# Filter_240MHz.net
KiCad netlist of a schematic drawn in Altium Designer
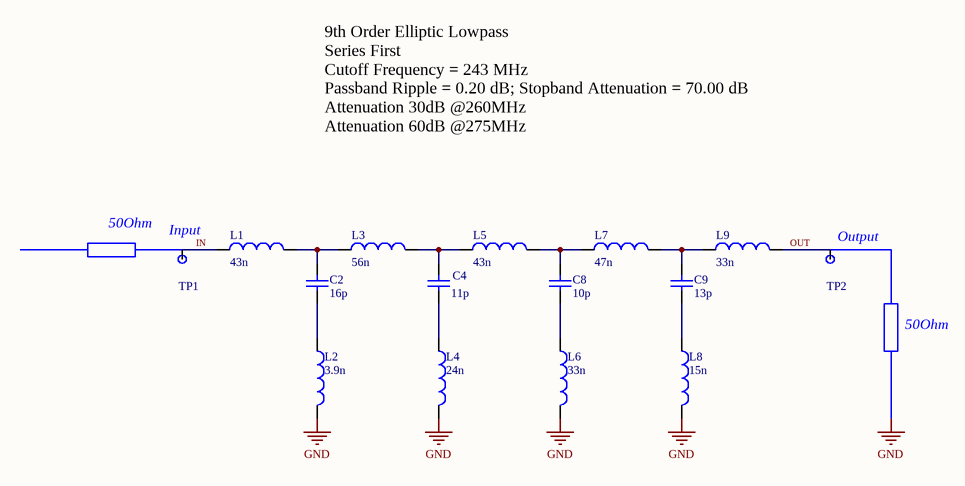
[diagram p0: Filter_240MHz.SchDoc]

(export (version "E")
  (design (tool "Eeschema 10.0.6"))
  (components
    (comp (ref "C2")
      (value "16p")
      (footprint "C0402")
      (description "16p 50V 0402")
      (fields (field (name "PART NUMBER") "CQ0402FRNPO9BN160") (field (name "VOLTAGE") "50V"))
      (libsource (lib "Capacitors") (part "1n_50V_0402"))
    )
    (comp (ref "C4")
      (value "11p")
      (footprint "C0402")
      (description "11p 50V 0402")
      (fields (field (name "PART NUMBER") "CC0402JRNPO9BN110") (field (name "VOLTAGE") "50V"))
      (libsource (lib "Capacitors") (part "1n_50V_0402"))
    )
    (comp (ref "C8")
      (value "10p")
      (footprint "C0402")
      (description "10p 50V 0402")
      (fields (field (name "PART NUMBER") "CQ0402FRNPO9BN100") (field (name "VOLTAGE") "50V"))
      (libsource (lib "Capacitors") (part "1n_50V_0402"))
    )
    (comp (ref "C9")
      (value "13p")
      (footprint "C0402")
      (description "13p 50V 0402")
      (fields (field (name "PART NUMBER") "CC0402JRNPO9BN130") (field (name "VOLTAGE") "50V"))
      (libsource (lib "Capacitors") (part "1n_50V_0402"))
    )
    (comp (ref "L1")
      (value "43n")
      (footprint "R0402")
      (description "43n 0402 0.7Ohm")
      (fields (field (name "PART NUMBER") "0402HM-430EGTS"))
      (libsource (lib "Inductors") (part "0402HC-3N9ECTS"))
    )
    (comp (ref "L2")
      (value "3.9n")
      (footprint "R0402")
      (description "3.9n 0402")
      (fields (field (name "PART NUMBER") "0402HC-3N9ECTS"))
      (libsource (lib "Inductors") (part "0402HC-3N9ECTS"))
    )
    (comp (ref "L3")
      (value "56n")
      (footprint "R0402")
      (description "56n 0402 1.17Ohm")
      (fields (field (name "PART NUMBER") "0402HM-560EGTS"))
      (libsource (lib "Inductors") (part "0402HC-3N9ECTS"))
    )
    (comp (ref "L4")
      (value "24n")
      (footprint "R0402")
      (description "24n 0402 0.53Ohm")
      (fields (field (name "PART NUMBER") "LQW15AN24NJ00D"))
      (libsource (lib "Inductors") (part "0402HC-3N9ECTS"))
    )
    (comp (ref "L5")
      (value "43n")
      (footprint "R0402")
      (description "43n 0402 0.7Ohm")
      (fields (field (name "PART NUMBER") "0402HM-430EGTS"))
      (libsource (lib "Inductors") (part "0402HC-3N9ECTS"))
    )
    (comp (ref "L6")
      (value "33n")
      (footprint "R0402")
      (description "33n 0402 0.63Ohm")
      (fields (field (name "PART NUMBER") "LQW15AN33NJ00D"))
      (libsource (lib "Inductors") (part "0402HC-3N9ECTS"))
    )
    (comp (ref "L7")
      (value "47n")
      (footprint "R0402")
      (description "47n 0402 0.72Ohm")
      (fields (field (name "PART NUMBER") "LQG15HS47NJ02D"))
      (libsource (lib "Inductors") (part "0402HC-3N9ECTS"))
    )
    (comp (ref "L8")
      (value "15n")
      (footprint "R0402")
      (description "15n 0402 0.16Ohm")
      (fields (field (name "PART NUMBER") "LQW15AN15NG00D"))
      (libsource (lib "Inductors") (part "0402HC-3N9ECTS"))
    )
    (comp (ref "L9")
      (value "33n")
      (footprint "R0402")
      (description "33n 0402 0.63Ohm")
      (fields (field (name "PART NUMBER") "LQW15AN33NJ00D"))
      (libsource (lib "Inductors") (part "0402HC-3N9ECTS"))
    )
    (comp (ref "TP1") (value "TP1mm") (footprint "TP1mm") (libsource (lib "Discrete") (part "TP1mm")))
    (comp (ref "TP2") (value "TP1mm") (footprint "TP1mm") (libsource (lib "Discrete") (part "TP1mm")))
  )
  (nets
    (net (code "1") (name "/IN") (class "Default")
      (node (ref "L1") (pin "1") (pinfunction "1_1") (pintype "passive"))
      (node (ref "TP1") (pin "1") (pinfunction "1_1") (pintype "passive"))
    )
    (net (code "2") (name "/OUT") (class "Default")
      (node (ref "L9") (pin "2") (pinfunction "2_2") (pintype "passive"))
      (node (ref "TP2") (pin "1") (pinfunction "1_1") (pintype "passive"))
    )
    (net (code "3") (name "GND") (class "Default")
      (node (ref "L2") (pin "2") (pinfunction "2_2") (pintype "passive"))
      (node (ref "L4") (pin "2") (pinfunction "2_2") (pintype "passive"))
      (node (ref "L6") (pin "2") (pinfunction "2_2") (pintype "passive"))
      (node (ref "L8") (pin "2") (pinfunction "2_2") (pintype "passive"))
    )
    (net (code "4") (name "Net-(C2-Pad1)") (class "Default")
      (node (ref "C2") (pin "1") (pinfunction "1_1") (pintype "passive"))
      (node (ref "L1") (pin "2") (pinfunction "2_2") (pintype "passive"))
      (node (ref "L3") (pin "1") (pinfunction "1_1") (pintype "passive"))
    )
    (net (code "5") (name "Net-(C2-Pad2)") (class "Default")
      (node (ref "C2") (pin "2") (pinfunction "2_2") (pintype "passive"))
      (node (ref "L2") (pin "1") (pinfunction "1_1") (pintype "passive"))
    )
    (net (code "6") (name "Net-(C4-Pad1)") (class "Default")
      (node (ref "C4") (pin "1") (pinfunction "1_1") (pintype "passive"))
      (node (ref "L3") (pin "2") (pinfunction "2_2") (pintype "passive"))
      (node (ref "L5") (pin "1") (pinfunction "1_1") (pintype "passive"))
    )
    (net (code "7") (name "Net-(C4-Pad2)") (class "Default")
      (node (ref "C4") (pin "2") (pinfunction "2_2") (pintype "passive"))
      (node (ref "L4") (pin "1") (pinfunction "1_1") (pintype "passive"))
    )
    (net (code "8") (name "Net-(C8-Pad1)") (class "Default")
      (node (ref "C8") (pin "1") (pinfunction "1_1") (pintype "passive"))
      (node (ref "L5") (pin "2") (pinfunction "2_2") (pintype "passive"))
      (node (ref "L7") (pin "1") (pinfunction "1_1") (pintype "passive"))
    )
    (net (code "9") (name "Net-(C8-Pad2)") (class "Default")
      (node (ref "C8") (pin "2") (pinfunction "2_2") (pintype "passive"))
      (node (ref "L6") (pin "1") (pinfunction "1_1") (pintype "passive"))
    )
    (net (code "10") (name "Net-(C9-Pad1)") (class "Default")
      (node (ref "C9") (pin "1") (pinfunction "1_1") (pintype "passive"))
      (node (ref "L7") (pin "2") (pinfunction "2_2") (pintype "passive"))
      (node (ref "L9") (pin "1") (pinfunction "1_1") (pintype "passive"))
    )
    (net (code "11") (name "Net-(C9-Pad2)") (class "Default")
      (node (ref "C9") (pin "2") (pinfunction "2_2") (pintype "passive"))
      (node (ref "L8") (pin "1") (pinfunction "1_1") (pintype "passive"))
    )
  )
)
